# 01-SURGE_PROTECT.net
KiCad netlist of a schematic drawn in Altium Designer
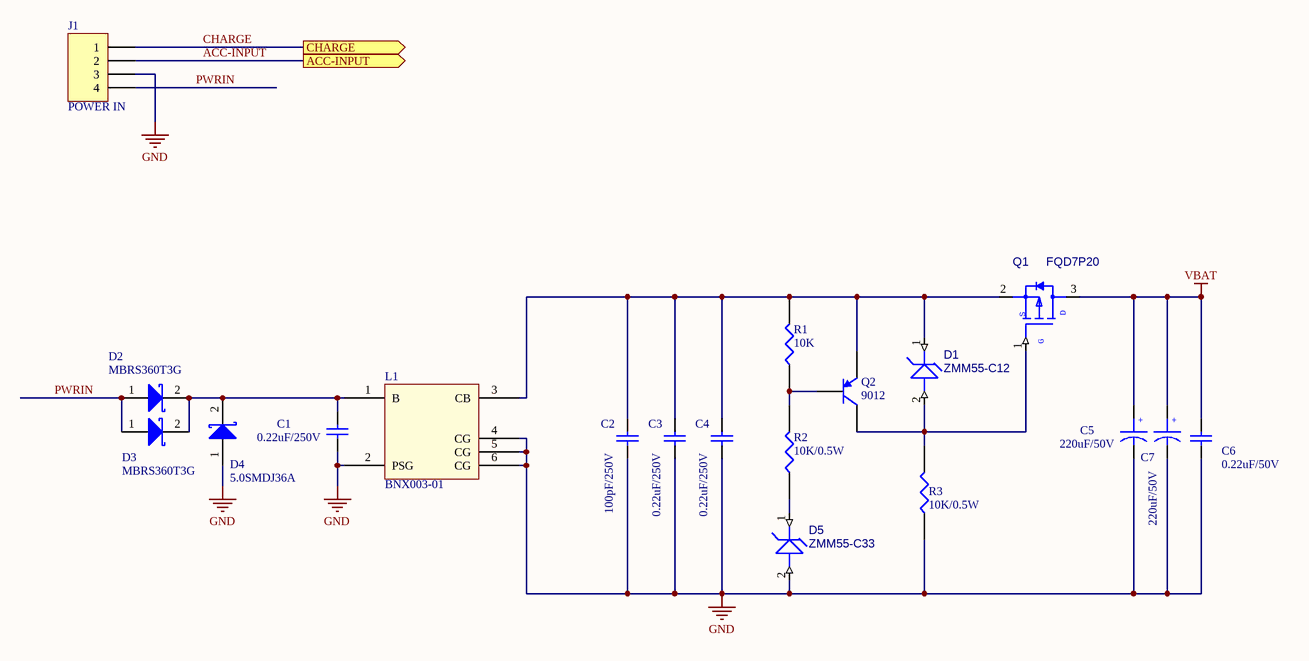
[diagram p0: 01-SURGE_PROTECT.SchDoc]

(export (version "E")
  (design (tool "Eeschema 10.0.6"))
  (components
    (comp (ref "C1")
      (value "0.22uF/250V")
      (footprint "1210")
      (description "Capacitor")
      (fields (field (name "PUBLISHER") "Altium Limited"))
      (libsource (lib "Miscellaneous Devices") (part "Cap"))
    )
    (comp (ref "C2")
      (value "100pF/250V")
      (footprint "0805")
      (description "Capacitor")
      (fields (field (name "PUBLISHER") "Altium Limited"))
      (libsource (lib "Miscellaneous Devices") (part "Cap"))
    )
    (comp (ref "C3")
      (value "0.22uF/250V")
      (footprint "1210")
      (description "Capacitor")
      (fields (field (name "PUBLISHER") "Altium Limited"))
      (libsource (lib "Miscellaneous Devices") (part "Cap"))
    )
    (comp (ref "C4")
      (value "0.22uF/250V")
      (footprint "1210")
      (description "Capacitor")
      (fields (field (name "PUBLISHER") "Altium Limited"))
      (libsource (lib "Miscellaneous Devices") (part "Cap"))
    )
    (comp (ref "C5") (value "220uF/50V") (footprint "DL-10*10.5") (libsource (lib "*") (part "CAP WP")))
    (comp (ref "C6")
      (value "0.22uF/50V")
      (footprint "0603")
      (description "Capacitor")
      (fields (field (name "PUBLISHER") "Altium Limited"))
      (libsource (lib "Miscellaneous Devices") (part "Cap"))
    )
    (comp (ref "C7") (value "220uF/50V") (footprint "DL-10*10.5") (libsource (lib "*") (part "CAP WP")))
    (comp (ref "D1")
      (value "ZMM55-C12")
      (footprint "MINI-MELF")
      (libsource (lib "*") (part "MMGZ5231BPTLL34"))
    )
    (comp (ref "D2")
      (value "MBRS360T3G")
      (footprint "SMC")
      (description "Schottky Rectifier")
      (libsource (lib "Miscellaneous Devices") (part "Diode 11DQ03"))
    )
    (comp (ref "D3")
      (value "MBRS360T3G")
      (footprint "SMC")
      (description "Schottky Rectifier")
      (libsource (lib "Miscellaneous Devices") (part "Diode 11DQ03"))
    )
    (comp (ref "D4")
      (value "5.0SMDJ36A")
      (footprint "SMC")
      (description "Schottky Rectifier")
      (libsource (lib "Miscellaneous Devices") (part "Diode 11DQ03"))
    )
    (comp (ref "D5")
      (value "ZMM55-C33")
      (footprint "MINI-MELF")
      (libsource (lib "*") (part "MMGZ5231BPTLL34"))
    )
    (comp (ref "J1")
      (value "POWER IN")
      (footprint "3030WV-F-2*2P")
      (description "Header, 4-Pin")
      (fields (field (name "PUBLISHER") "Altium Limited"))
      (libsource (lib "Miscellaneous Connectors") (part "Header 4"))
    )
    (comp (ref "L1")
      (value "BNX003-01")
      (footprint "BNX002-001")
      (libsource (lib "Schlib") (part "BNX002-01"))
    )
    (comp (ref "Q1")
      (value "FQD7P20")
      (footprint "FQD7P20")
      (fields (field (name "PART NUMBER") "SB934010010"))
      (libsource (lib "*") (part "AO3401L_SOT23-3_0"))
    )
    (comp (ref "Q2")
      (value "9012")
      (footprint "NPN")
      (description "PNP Bipolar Transistor")
      (fields (field (name "PUBLISHER") "Altium Limited"))
      (libsource (lib "Miscellaneous Devices") (part "PNP"))
    )
    (comp (ref "R1") (value "10K") (footprint "0402") (libsource (lib "*") (part "RES1")))
    (comp (ref "R2") (value "10K/0.5W") (footprint "1812") (libsource (lib "*") (part "RES1")))
    (comp (ref "R3") (value "10K/0.5W") (footprint "1812") (libsource (lib "*") (part "RES1")))
  )
  (nets
    (net (code "1") (name "/ACC-INPUT") (class "Default")
      (node (ref "J1") (pin "2") (pinfunction "2_2") (pintype "passive"))
    )
    (net (code "2") (name "/CHARGE") (class "Default")
      (node (ref "J1") (pin "1") (pinfunction "1_1") (pintype "passive"))
    )
    (net (code "3") (name "/PWRIN") (class "Default")
      (node (ref "D2") (pin "1") (pinfunction "A_1") (pintype "passive"))
      (node (ref "D3") (pin "1") (pinfunction "A_1") (pintype "passive"))
      (node (ref "J1") (pin "4") (pinfunction "4_4") (pintype "passive"))
    )
    (net (code "4") (name "GND") (class "Default")
      (node (ref "C1") (pin "2") (pinfunction "2_2") (pintype "passive"))
      (node (ref "C2") (pin "2") (pinfunction "2_2") (pintype "passive"))
      (node (ref "C3") (pin "2") (pinfunction "2_2") (pintype "passive"))
      (node (ref "C4") (pin "2") (pinfunction "2_2") (pintype "passive"))
      (node (ref "C5") (pin "2") (pinfunction "2_2") (pintype "passive"))
      (node (ref "C6") (pin "2") (pinfunction "2_2") (pintype "passive"))
      (node (ref "C7") (pin "2") (pinfunction "2_2") (pintype "passive"))
      (node (ref "D4") (pin "1") (pinfunction "A_1") (pintype "passive"))
      (node (ref "D5") (pin "2") (pinfunction "2_2") (pintype "input"))
      (node (ref "J1") (pin "3") (pinfunction "3_3") (pintype "passive"))
      (node (ref "L1") (pin "2") (pinfunction "PSG_2") (pintype "passive"))
      (node (ref "L1") (pin "4") (pinfunction "CG_4") (pintype "passive"))
      (node (ref "L1") (pin "5") (pinfunction "CG_5") (pintype "passive"))
      (node (ref "L1") (pin "6") (pinfunction "CG_6") (pintype "passive"))
      (node (ref "R3") (pin "1") (pinfunction "1_1") (pintype "passive"))
    )
    (net (code "5") (name "Net-(D2-K)") (class "Default")
      (node (ref "C1") (pin "1") (pinfunction "1_1") (pintype "passive"))
      (node (ref "D2") (pin "2") (pinfunction "K_2") (pintype "passive"))
      (node (ref "D3") (pin "2") (pinfunction "K_2") (pintype "passive"))
      (node (ref "D4") (pin "2") (pinfunction "K_2") (pintype "passive"))
      (node (ref "L1") (pin "1") (pinfunction "B_1") (pintype "passive"))
    )
    (net (code "6") (name "Net-(D5-Pad1)") (class "Default")
      (node (ref "D5") (pin "1") (pinfunction "1_1") (pintype "input"))
      (node (ref "R2") (pin "1") (pinfunction "1_1") (pintype "passive"))
    )
    (net (code "7") (name "Net-(L1-CB)") (class "Default")
      (node (ref "C2") (pin "1") (pinfunction "1_1") (pintype "passive"))
      (node (ref "C3") (pin "1") (pinfunction "1_1") (pintype "passive"))
      (node (ref "C4") (pin "1") (pinfunction "1_1") (pintype "passive"))
      (node (ref "D1") (pin "1") (pinfunction "1_1") (pintype "input"))
      (node (ref "L1") (pin "3") (pinfunction "CB_3") (pintype "passive"))
      (node (ref "Q1") (pin "2") (pinfunction "S_2") (pintype "passive"))
      (node (ref "Q2") (pin "3") (pinfunction "E_3") (pintype "passive"))
      (node (ref "R1") (pin "2") (pinfunction "2_2") (pintype "passive"))
    )
    (net (code "8") (name "Net-(Q1-G)") (class "Default")
      (node (ref "D1") (pin "2") (pinfunction "2_2") (pintype "input"))
      (node (ref "Q1") (pin "1") (pinfunction "G_1") (pintype "input"))
      (node (ref "Q2") (pin "1") (pinfunction "C_1") (pintype "passive"))
      (node (ref "R3") (pin "2") (pinfunction "2_2") (pintype "passive"))
    )
    (net (code "9") (name "Net-(Q2-B)") (class "Default")
      (node (ref "Q2") (pin "2") (pinfunction "B_2") (pintype "passive"))
      (node (ref "R1") (pin "1") (pinfunction "1_1") (pintype "passive"))
      (node (ref "R2") (pin "2") (pinfunction "2_2") (pintype "passive"))
    )
    (net (code "10") (name "VBAT") (class "Default")
      (node (ref "C5") (pin "1") (pinfunction "1_1") (pintype "passive"))
      (node (ref "C6") (pin "1") (pinfunction "1_1") (pintype "passive"))
      (node (ref "C7") (pin "1") (pinfunction "1_1") (pintype "passive"))
      (node (ref "Q1") (pin "3") (pinfunction "D_3") (pintype "passive"))
    )
  )
)
